# SCH_TSOP-32_Adapter_2022-05-23.net
KiCad netlist of a schematic drawn in EasyEDA
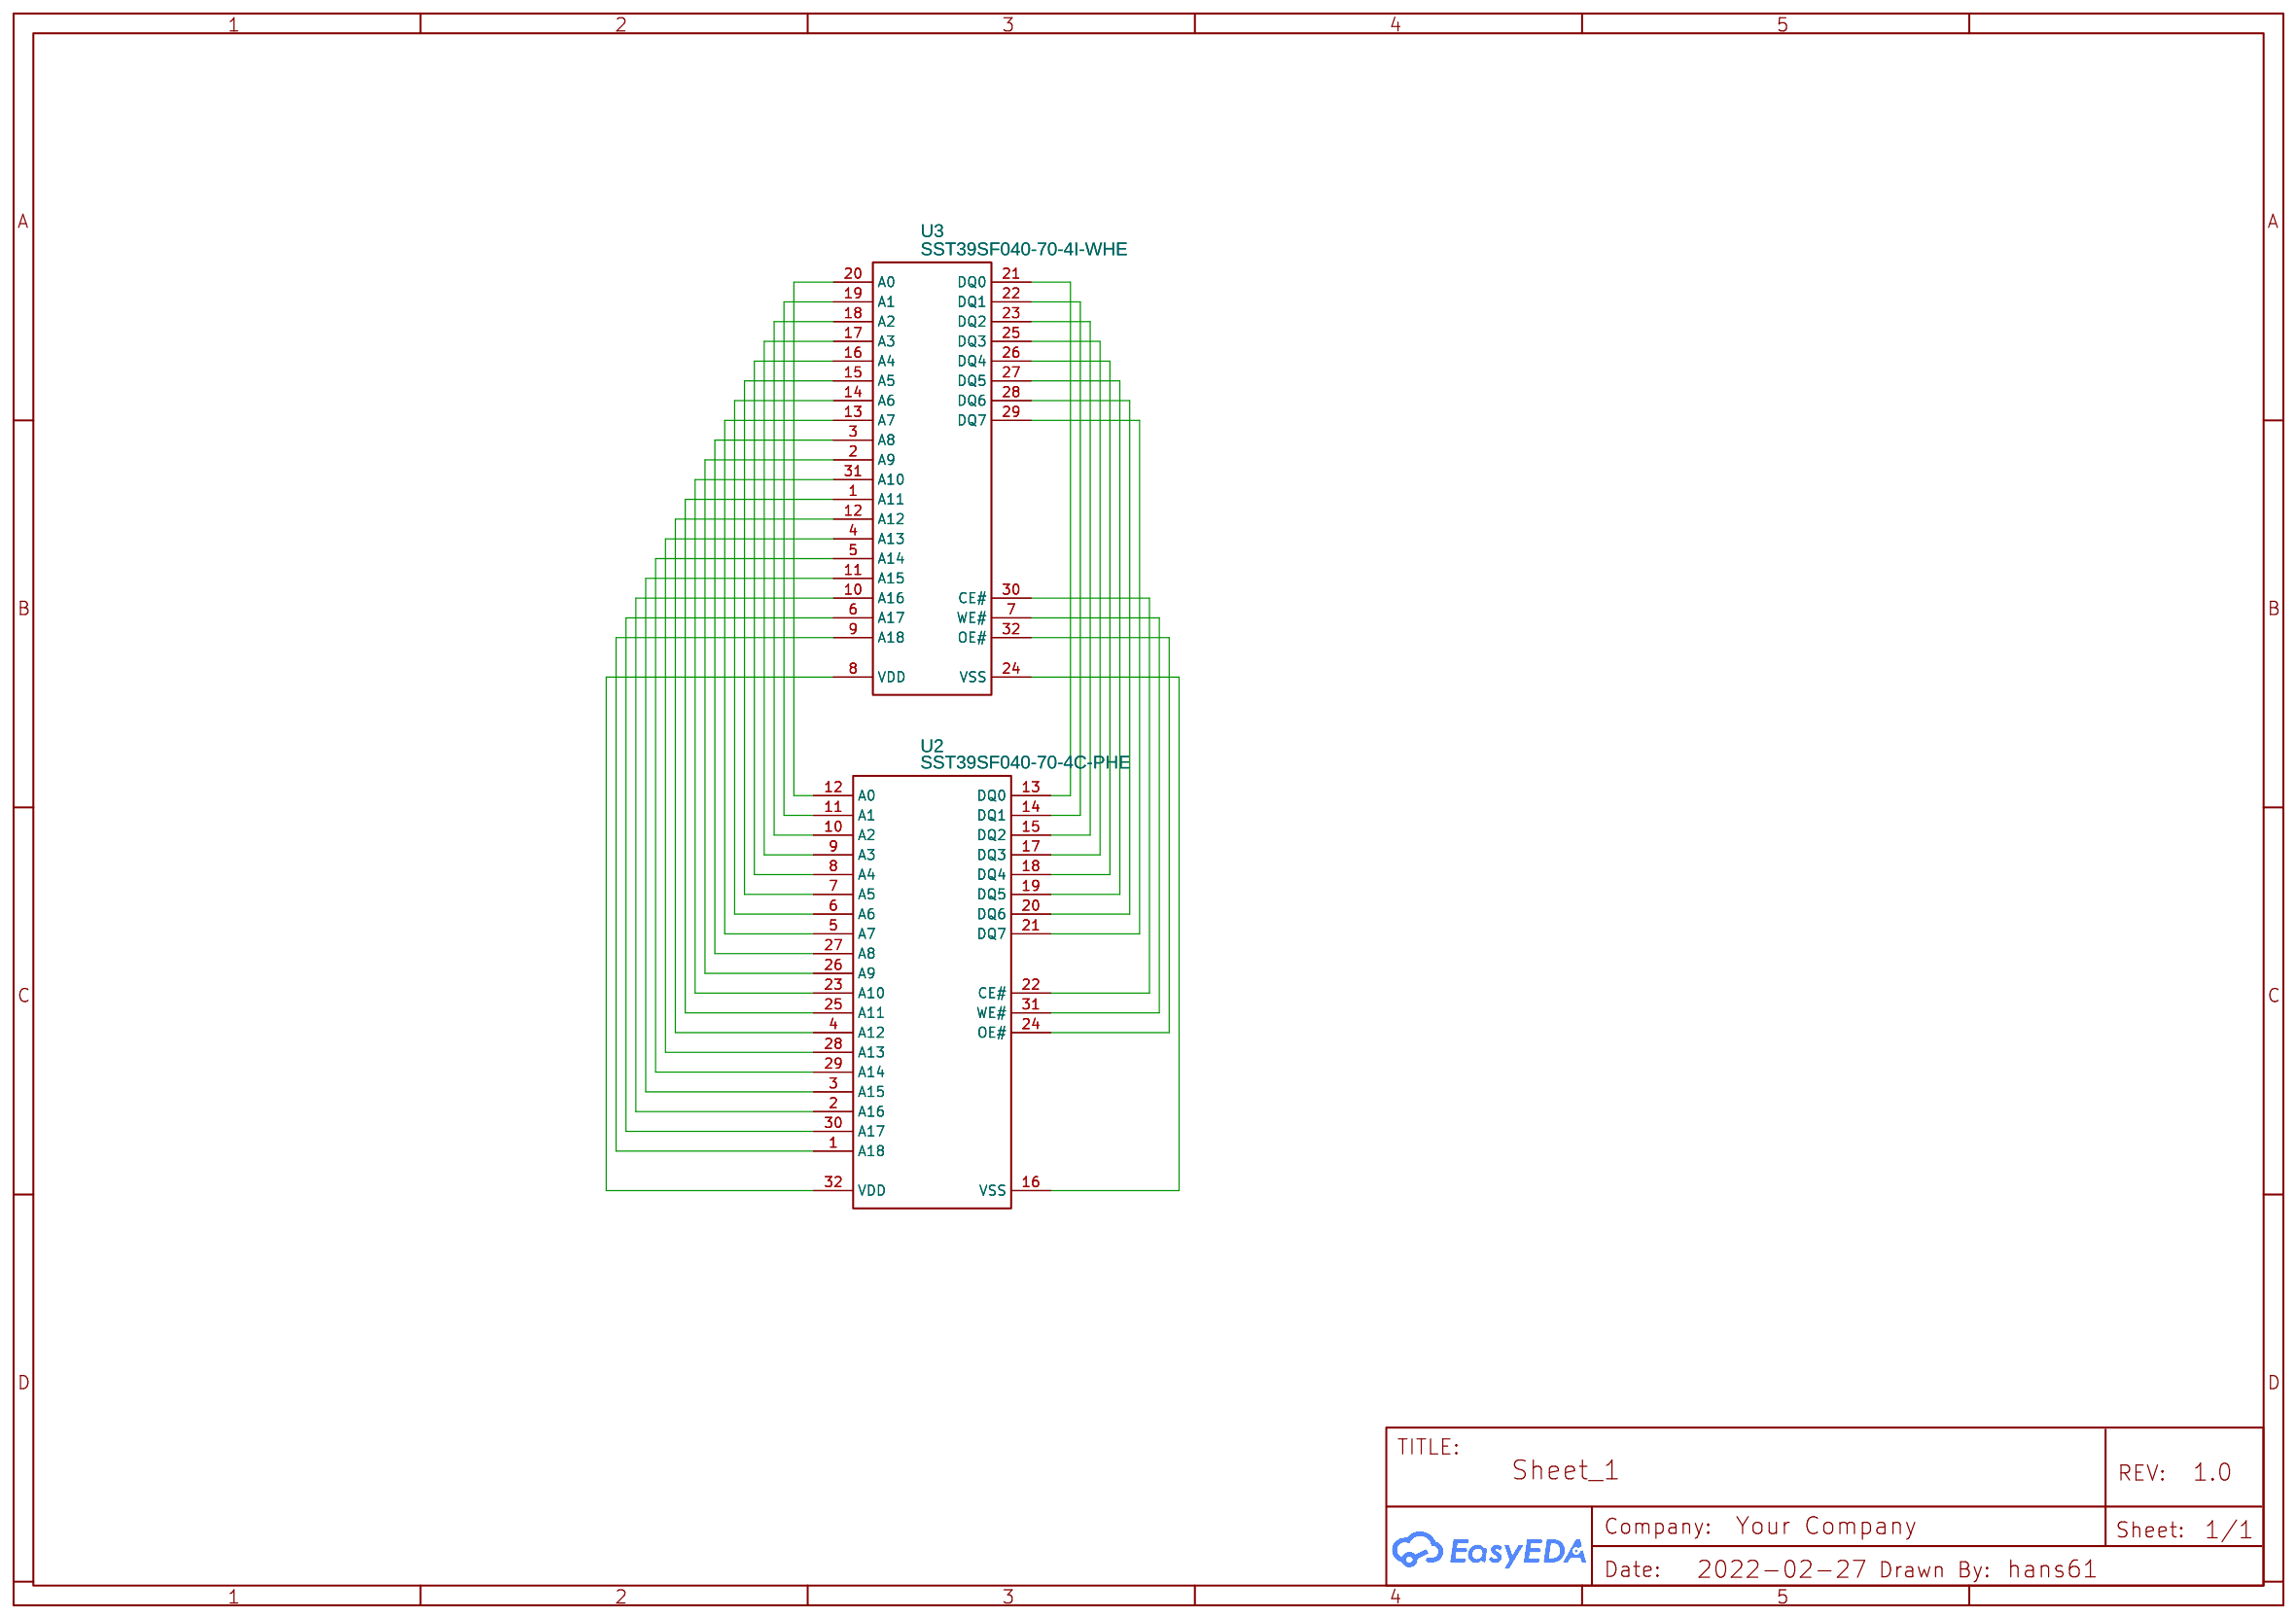
[diagram p0: schematic sheet]

(export (version "E")
  (design (tool "Eeschema 10.0.6"))
  (components
    (comp (ref "U2") (value "SST39SF040-70-4C-PHE") (libsource (lib "") (part "SST39SF040-70-4C-PHE")))
    (comp (ref "U3") (value "SST39SF040-70-4I-WHE") (libsource (lib "") (part "SST39SF040-70-4I-WHE")))
  )
  (nets
    (net (code "1") (name "Net-(U2-A0)") (class "Default")
      (node (ref "U2") (pin "12") (pinfunction "A0_12") (pintype "unspecified"))
      (node (ref "U3") (pin "20") (pinfunction "A0_20") (pintype "unspecified"))
    )
    (net (code "2") (name "Net-(U2-A1)") (class "Default")
      (node (ref "U2") (pin "11") (pinfunction "A1_11") (pintype "unspecified"))
      (node (ref "U3") (pin "19") (pinfunction "A1_19") (pintype "unspecified"))
    )
    (net (code "3") (name "Net-(U2-A2)") (class "Default")
      (node (ref "U2") (pin "10") (pinfunction "A2_10") (pintype "unspecified"))
      (node (ref "U3") (pin "18") (pinfunction "A2_18") (pintype "unspecified"))
    )
    (net (code "4") (name "Net-(U2-A3)") (class "Default")
      (node (ref "U2") (pin "9") (pinfunction "A3_9") (pintype "unspecified"))
      (node (ref "U3") (pin "17") (pinfunction "A3_17") (pintype "unspecified"))
    )
    (net (code "5") (name "Net-(U2-A4)") (class "Default")
      (node (ref "U2") (pin "8") (pinfunction "A4_8") (pintype "unspecified"))
      (node (ref "U3") (pin "16") (pinfunction "A4_16") (pintype "unspecified"))
    )
    (net (code "6") (name "Net-(U2-A5)") (class "Default")
      (node (ref "U2") (pin "7") (pinfunction "A5_7") (pintype "unspecified"))
      (node (ref "U3") (pin "15") (pinfunction "A5_15") (pintype "unspecified"))
    )
    (net (code "7") (name "Net-(U2-A6)") (class "Default")
      (node (ref "U2") (pin "6") (pinfunction "A6_6") (pintype "unspecified"))
      (node (ref "U3") (pin "14") (pinfunction "A6_14") (pintype "unspecified"))
    )
    (net (code "8") (name "Net-(U2-A7)") (class "Default")
      (node (ref "U2") (pin "5") (pinfunction "A7_5") (pintype "unspecified"))
      (node (ref "U3") (pin "13") (pinfunction "A7_13") (pintype "unspecified"))
    )
    (net (code "9") (name "Net-(U2-A8)") (class "Default")
      (node (ref "U2") (pin "27") (pinfunction "A8_27") (pintype "unspecified"))
      (node (ref "U3") (pin "3") (pinfunction "A8_3") (pintype "unspecified"))
    )
    (net (code "10") (name "Net-(U2-A9)") (class "Default")
      (node (ref "U2") (pin "26") (pinfunction "A9_26") (pintype "unspecified"))
      (node (ref "U3") (pin "2") (pinfunction "A9_2") (pintype "unspecified"))
    )
    (net (code "11") (name "Net-(U2-A10)") (class "Default")
      (node (ref "U2") (pin "23") (pinfunction "A10_23") (pintype "unspecified"))
      (node (ref "U3") (pin "31") (pinfunction "A10_31") (pintype "unspecified"))
    )
    (net (code "12") (name "Net-(U2-A11)") (class "Default")
      (node (ref "U2") (pin "25") (pinfunction "A11_25") (pintype "unspecified"))
      (node (ref "U3") (pin "1") (pinfunction "A11_1") (pintype "unspecified"))
    )
    (net (code "13") (name "Net-(U2-A12)") (class "Default")
      (node (ref "U2") (pin "4") (pinfunction "A12_4") (pintype "unspecified"))
      (node (ref "U3") (pin "12") (pinfunction "A12_12") (pintype "unspecified"))
    )
    (net (code "14") (name "Net-(U2-A13)") (class "Default")
      (node (ref "U2") (pin "28") (pinfunction "A13_28") (pintype "unspecified"))
      (node (ref "U3") (pin "4") (pinfunction "A13_4") (pintype "unspecified"))
    )
    (net (code "15") (name "Net-(U2-A14)") (class "Default")
      (node (ref "U2") (pin "29") (pinfunction "A14_29") (pintype "unspecified"))
      (node (ref "U3") (pin "5") (pinfunction "A14_5") (pintype "unspecified"))
    )
    (net (code "16") (name "Net-(U2-A15)") (class "Default")
      (node (ref "U2") (pin "3") (pinfunction "A15_3") (pintype "unspecified"))
      (node (ref "U3") (pin "11") (pinfunction "A15_11") (pintype "unspecified"))
    )
    (net (code "17") (name "Net-(U2-A16)") (class "Default")
      (node (ref "U2") (pin "2") (pinfunction "A16_2") (pintype "unspecified"))
      (node (ref "U3") (pin "10") (pinfunction "A16_10") (pintype "unspecified"))
    )
    (net (code "18") (name "Net-(U2-A17)") (class "Default")
      (node (ref "U2") (pin "30") (pinfunction "A17_30") (pintype "unspecified"))
      (node (ref "U3") (pin "6") (pinfunction "A17_6") (pintype "unspecified"))
    )
    (net (code "19") (name "Net-(U2-A18)") (class "Default")
      (node (ref "U2") (pin "1") (pinfunction "A18_1") (pintype "unspecified"))
      (node (ref "U3") (pin "9") (pinfunction "A18_9") (pintype "unspecified"))
    )
    (net (code "20") (name "Net-(U2-CE#)") (class "Default")
      (node (ref "U2") (pin "22") (pinfunction "CE#_22") (pintype "unspecified"))
      (node (ref "U3") (pin "30") (pinfunction "CE#_30") (pintype "unspecified"))
    )
    (net (code "21") (name "Net-(U2-DQ0)") (class "Default")
      (node (ref "U2") (pin "13") (pinfunction "DQ0_13") (pintype "bidirectional"))
      (node (ref "U3") (pin "21") (pinfunction "DQ0_21") (pintype "bidirectional"))
    )
    (net (code "22") (name "Net-(U2-DQ1)") (class "Default")
      (node (ref "U2") (pin "14") (pinfunction "DQ1_14") (pintype "bidirectional"))
      (node (ref "U3") (pin "22") (pinfunction "DQ1_22") (pintype "bidirectional"))
    )
    (net (code "23") (name "Net-(U2-DQ2)") (class "Default")
      (node (ref "U2") (pin "15") (pinfunction "DQ2_15") (pintype "bidirectional"))
      (node (ref "U3") (pin "23") (pinfunction "DQ2_23") (pintype "bidirectional"))
    )
    (net (code "24") (name "Net-(U2-DQ3)") (class "Default")
      (node (ref "U2") (pin "17") (pinfunction "DQ3_17") (pintype "bidirectional"))
      (node (ref "U3") (pin "25") (pinfunction "DQ3_25") (pintype "bidirectional"))
    )
    (net (code "25") (name "Net-(U2-DQ4)") (class "Default")
      (node (ref "U2") (pin "18") (pinfunction "DQ4_18") (pintype "bidirectional"))
      (node (ref "U3") (pin "26") (pinfunction "DQ4_26") (pintype "bidirectional"))
    )
    (net (code "26") (name "Net-(U2-DQ5)") (class "Default")
      (node (ref "U2") (pin "19") (pinfunction "DQ5_19") (pintype "bidirectional"))
      (node (ref "U3") (pin "27") (pinfunction "DQ5_27") (pintype "bidirectional"))
    )
    (net (code "27") (name "Net-(U2-DQ6)") (class "Default")
      (node (ref "U2") (pin "20") (pinfunction "DQ6_20") (pintype "bidirectional"))
      (node (ref "U3") (pin "28") (pinfunction "DQ6_28") (pintype "bidirectional"))
    )
    (net (code "28") (name "Net-(U2-DQ7)") (class "Default")
      (node (ref "U2") (pin "21") (pinfunction "DQ7_21") (pintype "bidirectional"))
      (node (ref "U3") (pin "29") (pinfunction "DQ7_29") (pintype "bidirectional"))
    )
    (net (code "29") (name "Net-(U2-OE#)") (class "Default")
      (node (ref "U2") (pin "24") (pinfunction "OE#_24") (pintype "unspecified"))
      (node (ref "U3") (pin "32") (pinfunction "OE#_32") (pintype "unspecified"))
    )
    (net (code "30") (name "Net-(U2-VDD)") (class "Default")
      (node (ref "U2") (pin "32") (pinfunction "VDD_32") (pintype "passive"))
      (node (ref "U3") (pin "8") (pinfunction "VDD_8") (pintype "passive"))
    )
    (net (code "31") (name "Net-(U2-VSS)") (class "Default")
      (node (ref "U2") (pin "16") (pinfunction "VSS_16") (pintype "passive"))
      (node (ref "U3") (pin "24") (pinfunction "VSS_24") (pintype "passive"))
    )
    (net (code "32") (name "Net-(U2-WE#)") (class "Default")
      (node (ref "U2") (pin "31") (pinfunction "WE#_31") (pintype "unspecified"))
      (node (ref "U3") (pin "7") (pinfunction "WE#_7") (pintype "unspecified"))
    )
  )
)
